# EMI_Detect_V1_0.net
KiCad netlist of a schematic drawn in EAGLE
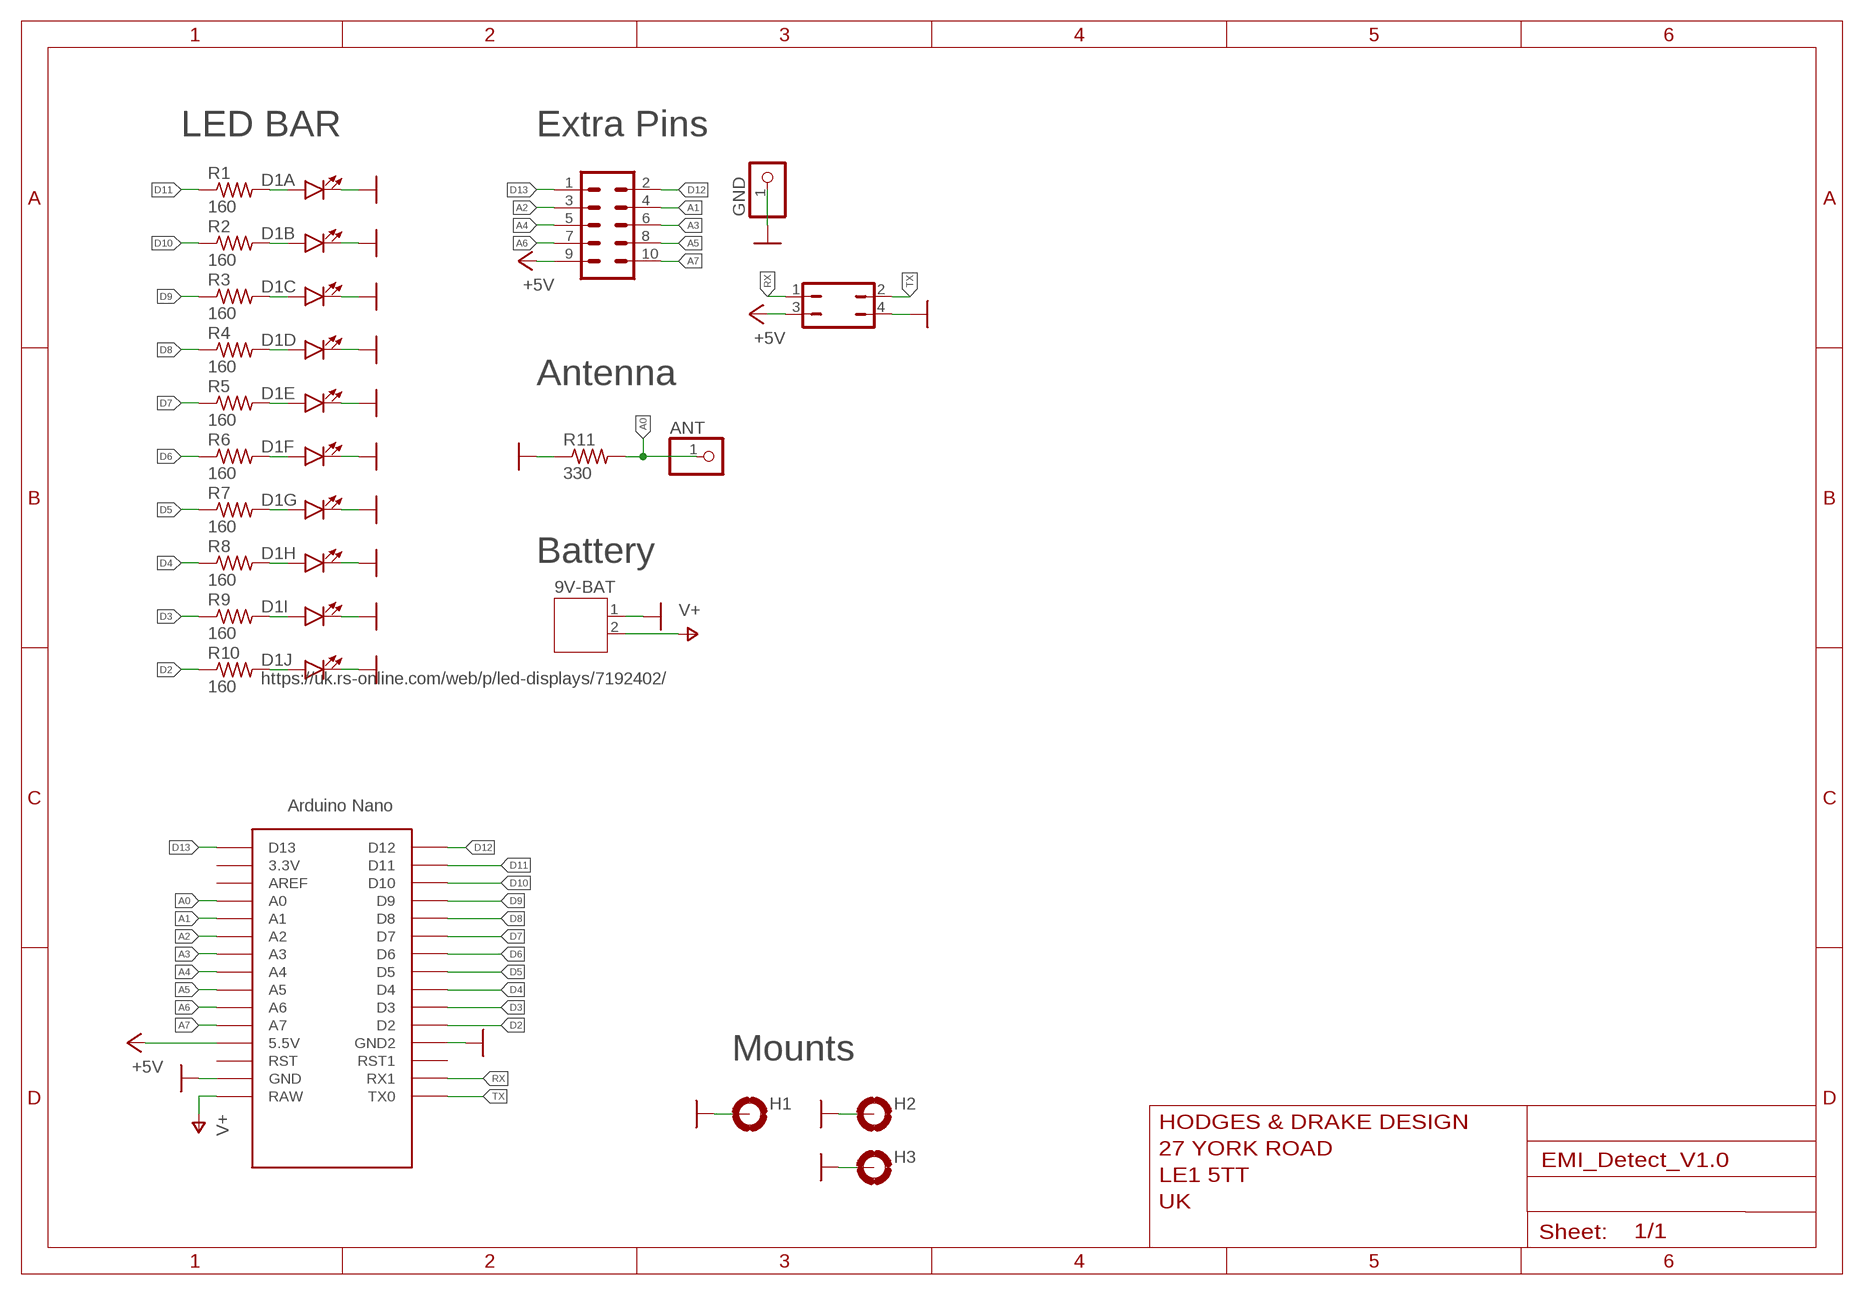
[diagram p0: schematic, sheet 1]

(export (version "E")
  (design (tool "Eeschema 10.0.6"))
  (components
    (comp (ref "9V-BAT")
      (value "JST-PH2")
      (footprint "eagle-import:JST-PH2-S2B")
      (libsource (lib "eagle-import") (part "JST-PH2"))
    )
    (comp (ref "ANT")
      (value "PINHD-1X1")
      (footprint "eagle-import:1X01")
      (libsource (lib "eagle-import") (part "PINHD-1X1"))
    )
    (comp (ref "D1")
      (value "https://uk.rs-online.com/web/p/led-displays/7192402/")
      (footprint "eagle-import:LED_BARGAPH_10")
      (libsource (lib "eagle-import") (part "LED_BARGRAPH_10"))
    )
    (comp (ref "GND")
      (value "PINHD-1X1")
      (footprint "eagle-import:1X01")
      (libsource (lib "eagle-import") (part "PINHD-1X1"))
    )
    (comp (ref "H1")
      (value "MOUNT-PAD-ROUND2.8")
      (footprint "eagle-import:2,8-PAD")
      (libsource (lib "eagle-import") (part "MOUNT-PAD-ROUND2.8"))
    )
    (comp (ref "H2")
      (value "MOUNT-PAD-ROUND2.8")
      (footprint "eagle-import:2,8-PAD")
      (libsource (lib "eagle-import") (part "MOUNT-PAD-ROUND2.8"))
    )
    (comp (ref "H3")
      (value "MOUNT-PAD-ROUND2.8")
      (footprint "eagle-import:2,8-PAD")
      (libsource (lib "eagle-import") (part "MOUNT-PAD-ROUND2.8"))
    )
    (comp (ref "JP1")
      (value "M05X2PTH")
      (footprint "eagle-import:AVR_ICSP")
      (libsource (lib "eagle-import") (part "M05X2PTH"))
    )
    (comp (ref "JP2")
      (value "JP2Q")
      (footprint "eagle-import:JP2Q")
      (libsource (lib "eagle-import") (part "JP2Q"))
    )
    (comp (ref "R1")
      (value "160")
      (footprint "eagle-import:0805-THM")
      (libsource (lib "eagle-import") (part "R-US_FLIPFLOP"))
    )
    (comp (ref "R2")
      (value "160")
      (footprint "eagle-import:0805-THM")
      (libsource (lib "eagle-import") (part "R-US_FLIPFLOP"))
    )
    (comp (ref "R3")
      (value "160")
      (footprint "eagle-import:0805-THM")
      (libsource (lib "eagle-import") (part "R-US_FLIPFLOP"))
    )
    (comp (ref "R4")
      (value "160")
      (footprint "eagle-import:0805-THM")
      (libsource (lib "eagle-import") (part "R-US_FLIPFLOP"))
    )
    (comp (ref "R5")
      (value "160")
      (footprint "eagle-import:0805-THM")
      (libsource (lib "eagle-import") (part "R-US_FLIPFLOP"))
    )
    (comp (ref "R6")
      (value "160")
      (footprint "eagle-import:0805-THM")
      (libsource (lib "eagle-import") (part "R-US_FLIPFLOP"))
    )
    (comp (ref "R7")
      (value "160")
      (footprint "eagle-import:0805-THM")
      (libsource (lib "eagle-import") (part "R-US_FLIPFLOP"))
    )
    (comp (ref "R8")
      (value "160")
      (footprint "eagle-import:0805-THM")
      (libsource (lib "eagle-import") (part "R-US_FLIPFLOP"))
    )
    (comp (ref "R9")
      (value "160")
      (footprint "eagle-import:0805-THM")
      (libsource (lib "eagle-import") (part "R-US_FLIPFLOP"))
    )
    (comp (ref "R10")
      (value "160")
      (footprint "eagle-import:0805-THM")
      (libsource (lib "eagle-import") (part "R-US_FLIPFLOP"))
    )
    (comp (ref "R11")
      (value "330")
      (footprint "eagle-import:0805-THM")
      (libsource (lib "eagle-import") (part "R-US_FLIPFLOP"))
    )
    (comp (ref "U$1")
      (value "NANO")
      (footprint "eagle-import:NANO")
      (libsource (lib "eagle-import") (part "NANO"))
    )
  )
  (nets
    (net (code "1") (name "+5V") (class "Default")
      (node (ref "JP1") (pin "9") (pinfunction "9_9") (pintype "passive"))
      (node (ref "JP2") (pin "3") (pinfunction "3_3") (pintype "passive"))
      (node (ref "U$1") (pin "5V") (pinfunction "5.5V_5V") (pintype "bidirectional"))
    )
    (net (code "2") (name "A0") (class "Default")
      (node (ref "ANT") (pin "1") (pinfunction "1_1") (pintype "passive"))
      (node (ref "R11") (pin "2") (pinfunction "2_2") (pintype "passive"))
      (node (ref "U$1") (pin "A0") (pinfunction "A0_A0") (pintype "bidirectional"))
    )
    (net (code "3") (name "A1") (class "Default")
      (node (ref "JP1") (pin "4") (pinfunction "4_4") (pintype "passive"))
      (node (ref "U$1") (pin "A1") (pinfunction "A1_A1") (pintype "bidirectional"))
    )
    (net (code "4") (name "A2") (class "Default")
      (node (ref "JP1") (pin "3") (pinfunction "3_3") (pintype "passive"))
      (node (ref "U$1") (pin "A2") (pinfunction "A2_A2") (pintype "bidirectional"))
    )
    (net (code "5") (name "A3") (class "Default")
      (node (ref "JP1") (pin "6") (pinfunction "6_6") (pintype "passive"))
      (node (ref "U$1") (pin "A3") (pinfunction "A3_A3") (pintype "bidirectional"))
    )
    (net (code "6") (name "A4") (class "Default")
      (node (ref "JP1") (pin "5") (pinfunction "5_5") (pintype "passive"))
      (node (ref "U$1") (pin "A4") (pinfunction "A4_A4") (pintype "bidirectional"))
    )
    (net (code "7") (name "A5") (class "Default")
      (node (ref "JP1") (pin "8") (pinfunction "8_8") (pintype "passive"))
      (node (ref "U$1") (pin "A5") (pinfunction "A5_A5") (pintype "bidirectional"))
    )
    (net (code "8") (name "A6") (class "Default")
      (node (ref "JP1") (pin "7") (pinfunction "7_7") (pintype "passive"))
      (node (ref "U$1") (pin "A6") (pinfunction "A6_A6") (pintype "bidirectional"))
    )
    (net (code "9") (name "A7") (class "Default")
      (node (ref "JP1") (pin "10") (pinfunction "10_10") (pintype "passive"))
      (node (ref "U$1") (pin "A7") (pinfunction "A7_A7") (pintype "bidirectional"))
    )
    (net (code "10") (name "D2") (class "Default")
      (node (ref "R10") (pin "1") (pinfunction "1_1") (pintype "passive"))
      (node (ref "U$1") (pin "D2") (pinfunction "D2_D2") (pintype "bidirectional"))
    )
    (net (code "11") (name "D3") (class "Default")
      (node (ref "R9") (pin "1") (pinfunction "1_1") (pintype "passive"))
      (node (ref "U$1") (pin "D3") (pinfunction "D3_D3") (pintype "bidirectional"))
    )
    (net (code "12") (name "D4") (class "Default")
      (node (ref "R8") (pin "1") (pinfunction "1_1") (pintype "passive"))
      (node (ref "U$1") (pin "D4") (pinfunction "D4_D4") (pintype "bidirectional"))
    )
    (net (code "13") (name "D5") (class "Default")
      (node (ref "R7") (pin "1") (pinfunction "1_1") (pintype "passive"))
      (node (ref "U$1") (pin "D5") (pinfunction "D5_D5") (pintype "bidirectional"))
    )
    (net (code "14") (name "D6") (class "Default")
      (node (ref "R6") (pin "1") (pinfunction "1_1") (pintype "passive"))
      (node (ref "U$1") (pin "D6") (pinfunction "D6_D6") (pintype "bidirectional"))
    )
    (net (code "15") (name "D7") (class "Default")
      (node (ref "R5") (pin "1") (pinfunction "1_1") (pintype "passive"))
      (node (ref "U$1") (pin "D7") (pinfunction "D7_D7") (pintype "bidirectional"))
    )
    (net (code "16") (name "D8") (class "Default")
      (node (ref "R4") (pin "1") (pinfunction "1_1") (pintype "passive"))
      (node (ref "U$1") (pin "D8") (pinfunction "D8_D8") (pintype "bidirectional"))
    )
    (net (code "17") (name "D9") (class "Default")
      (node (ref "R3") (pin "1") (pinfunction "1_1") (pintype "passive"))
      (node (ref "U$1") (pin "D9") (pinfunction "D9_D9") (pintype "bidirectional"))
    )
    (net (code "18") (name "D10") (class "Default")
      (node (ref "R2") (pin "1") (pinfunction "1_1") (pintype "passive"))
      (node (ref "U$1") (pin "D10") (pinfunction "D10_D10") (pintype "bidirectional"))
    )
    (net (code "19") (name "D11") (class "Default")
      (node (ref "R1") (pin "1") (pinfunction "1_1") (pintype "passive"))
      (node (ref "U$1") (pin "D11") (pinfunction "D11_D11") (pintype "bidirectional"))
    )
    (net (code "20") (name "D12") (class "Default")
      (node (ref "JP1") (pin "2") (pinfunction "2_2") (pintype "passive"))
      (node (ref "U$1") (pin "D12") (pinfunction "D12_D12") (pintype "bidirectional"))
    )
    (net (code "21") (name "D13") (class "Default")
      (node (ref "JP1") (pin "1") (pinfunction "1_1") (pintype "passive"))
      (node (ref "U$1") (pin "D13") (pinfunction "D13_D13") (pintype "bidirectional"))
    )
    (net (code "22") (name "GND") (class "Default")
      (node (ref "9V-BAT") (pin "1") (pinfunction "1_1") (pintype "passive"))
      (node (ref "D1") (pin "11") (pinfunction "C_11") (pintype "passive"))
      (node (ref "D1") (pin "12") (pinfunction "C_12") (pintype "passive"))
      (node (ref "D1") (pin "13") (pinfunction "C_13") (pintype "passive"))
      (node (ref "D1") (pin "14") (pinfunction "C_14") (pintype "passive"))
      (node (ref "D1") (pin "15") (pinfunction "C_15") (pintype "passive"))
      (node (ref "D1") (pin "16") (pinfunction "C_16") (pintype "passive"))
      (node (ref "D1") (pin "17") (pinfunction "C_17") (pintype "passive"))
      (node (ref "D1") (pin "18") (pinfunction "C_18") (pintype "passive"))
      (node (ref "D1") (pin "19") (pinfunction "C_19") (pintype "passive"))
      (node (ref "D1") (pin "20") (pinfunction "C_20") (pintype "passive"))
      (node (ref "GND") (pin "1") (pinfunction "1_1") (pintype "passive"))
      (node (ref "H1") (pin "B2,8") (pinfunction "MOUNT_B2,8") (pintype "passive"))
      (node (ref "H2") (pin "B2,8") (pinfunction "MOUNT_B2,8") (pintype "passive"))
      (node (ref "H3") (pin "B2,8") (pinfunction "MOUNT_B2,8") (pintype "passive"))
      (node (ref "JP2") (pin "4") (pinfunction "4_4") (pintype "passive"))
      (node (ref "R11") (pin "1") (pinfunction "1_1") (pintype "passive"))
      (node (ref "U$1") (pin "GND") (pinfunction "GND_GND") (pintype "bidirectional"))
      (node (ref "U$1") (pin "GND1") (pinfunction "GND2_GND1") (pintype "bidirectional"))
    )
    (net (code "23") (name "Net-(D1A-A)") (class "Default")
      (node (ref "D1") (pin "1") (pinfunction "A_1") (pintype "passive"))
      (node (ref "R1") (pin "2") (pinfunction "2_2") (pintype "passive"))
    )
    (net (code "24") (name "Net-(D1B-A)") (class "Default")
      (node (ref "D1") (pin "2") (pinfunction "A_2") (pintype "passive"))
      (node (ref "R2") (pin "2") (pinfunction "2_2") (pintype "passive"))
    )
    (net (code "25") (name "Net-(D1C-A)") (class "Default")
      (node (ref "D1") (pin "3") (pinfunction "A_3") (pintype "passive"))
      (node (ref "R3") (pin "2") (pinfunction "2_2") (pintype "passive"))
    )
    (net (code "26") (name "Net-(D1D-A)") (class "Default")
      (node (ref "D1") (pin "4") (pinfunction "A_4") (pintype "passive"))
      (node (ref "R4") (pin "2") (pinfunction "2_2") (pintype "passive"))
    )
    (net (code "27") (name "Net-(D1E-A)") (class "Default")
      (node (ref "D1") (pin "5") (pinfunction "A_5") (pintype "passive"))
      (node (ref "R5") (pin "2") (pinfunction "2_2") (pintype "passive"))
    )
    (net (code "28") (name "Net-(D1F-A)") (class "Default")
      (node (ref "D1") (pin "6") (pinfunction "A_6") (pintype "passive"))
      (node (ref "R6") (pin "2") (pinfunction "2_2") (pintype "passive"))
    )
    (net (code "29") (name "Net-(D1G-A)") (class "Default")
      (node (ref "D1") (pin "7") (pinfunction "A_7") (pintype "passive"))
      (node (ref "R7") (pin "2") (pinfunction "2_2") (pintype "passive"))
    )
    (net (code "30") (name "Net-(D1H-A)") (class "Default")
      (node (ref "D1") (pin "8") (pinfunction "A_8") (pintype "passive"))
      (node (ref "R8") (pin "2") (pinfunction "2_2") (pintype "passive"))
    )
    (net (code "31") (name "Net-(D1I-A)") (class "Default")
      (node (ref "D1") (pin "9") (pinfunction "A_9") (pintype "passive"))
      (node (ref "R9") (pin "2") (pinfunction "2_2") (pintype "passive"))
    )
    (net (code "32") (name "Net-(D1J-A)") (class "Default")
      (node (ref "D1") (pin "10") (pinfunction "A_10") (pintype "passive"))
      (node (ref "R10") (pin "2") (pinfunction "2_2") (pintype "passive"))
    )
    (net (code "33") (name "RX") (class "Default")
      (node (ref "JP2") (pin "1") (pinfunction "1_1") (pintype "passive"))
      (node (ref "U$1") (pin "RX1") (pinfunction "RX1_RX1") (pintype "bidirectional"))
    )
    (net (code "34") (name "TX") (class "Default")
      (node (ref "JP2") (pin "2") (pinfunction "2_2") (pintype "passive"))
      (node (ref "U$1") (pin "TX0") (pinfunction "TX0_TX0") (pintype "bidirectional"))
    )
    (net (code "35") (name "V+") (class "Default")
      (node (ref "9V-BAT") (pin "2") (pinfunction "2_2") (pintype "passive"))
      (node (ref "U$1") (pin "RAW") (pinfunction "RAW_RAW") (pintype "bidirectional"))
    )
    (net (code "36") (name "unconnected-(U$1-Pad3.3V)") (class "Default")
      (node (ref "U$1") (pin "3.3V") (pinfunction "3.3V_3.3V") (pintype "bidirectional"))
    )
    (net (code "37") (name "unconnected-(U$1-PadAREF)") (class "Default")
      (node (ref "U$1") (pin "AREF") (pinfunction "AREF_AREF") (pintype "bidirectional"))
    )
    (net (code "38") (name "unconnected-(U$1-PadICSP1)") (class "Default")
      (node (ref "U$1") (pin "ICSP1") (pinfunction "ICSP1_ICSP1") (pintype "bidirectional"))
    )
    (net (code "39") (name "unconnected-(U$1-PadICSP2)") (class "Default")
      (node (ref "U$1") (pin "ICSP2") (pinfunction "ICSP2_ICSP2") (pintype "bidirectional"))
    )
    (net (code "40") (name "unconnected-(U$1-PadICSP3)") (class "Default")
      (node (ref "U$1") (pin "ICSP3") (pinfunction "ICSP3_ICSP3") (pintype "bidirectional"))
    )
    (net (code "41") (name "unconnected-(U$1-PadICSP4)") (class "Default")
      (node (ref "U$1") (pin "ICSP4") (pinfunction "ICSP4_ICSP4") (pintype "bidirectional"))
    )
    (net (code "42") (name "unconnected-(U$1-PadICSP5)") (class "Default")
      (node (ref "U$1") (pin "ICSP5") (pinfunction "ICSP5_ICSP5") (pintype "bidirectional"))
    )
    (net (code "43") (name "unconnected-(U$1-PadICSP6)") (class "Default")
      (node (ref "U$1") (pin "ICSP6") (pinfunction "ICSP6_ICSP6") (pintype "bidirectional"))
    )
    (net (code "44") (name "unconnected-(U$1-PadRST)") (class "Default")
      (node (ref "U$1") (pin "RST") (pinfunction "RST_RST") (pintype "bidirectional"))
    )
    (net (code "45") (name "unconnected-(U$1-PadRST1)") (class "Default")
      (node (ref "U$1") (pin "RST1") (pinfunction "RST1_RST1") (pintype "bidirectional"))
    )
  )
)
